# M515X.net
KiCad netlist of a schematic drawn in EAGLE
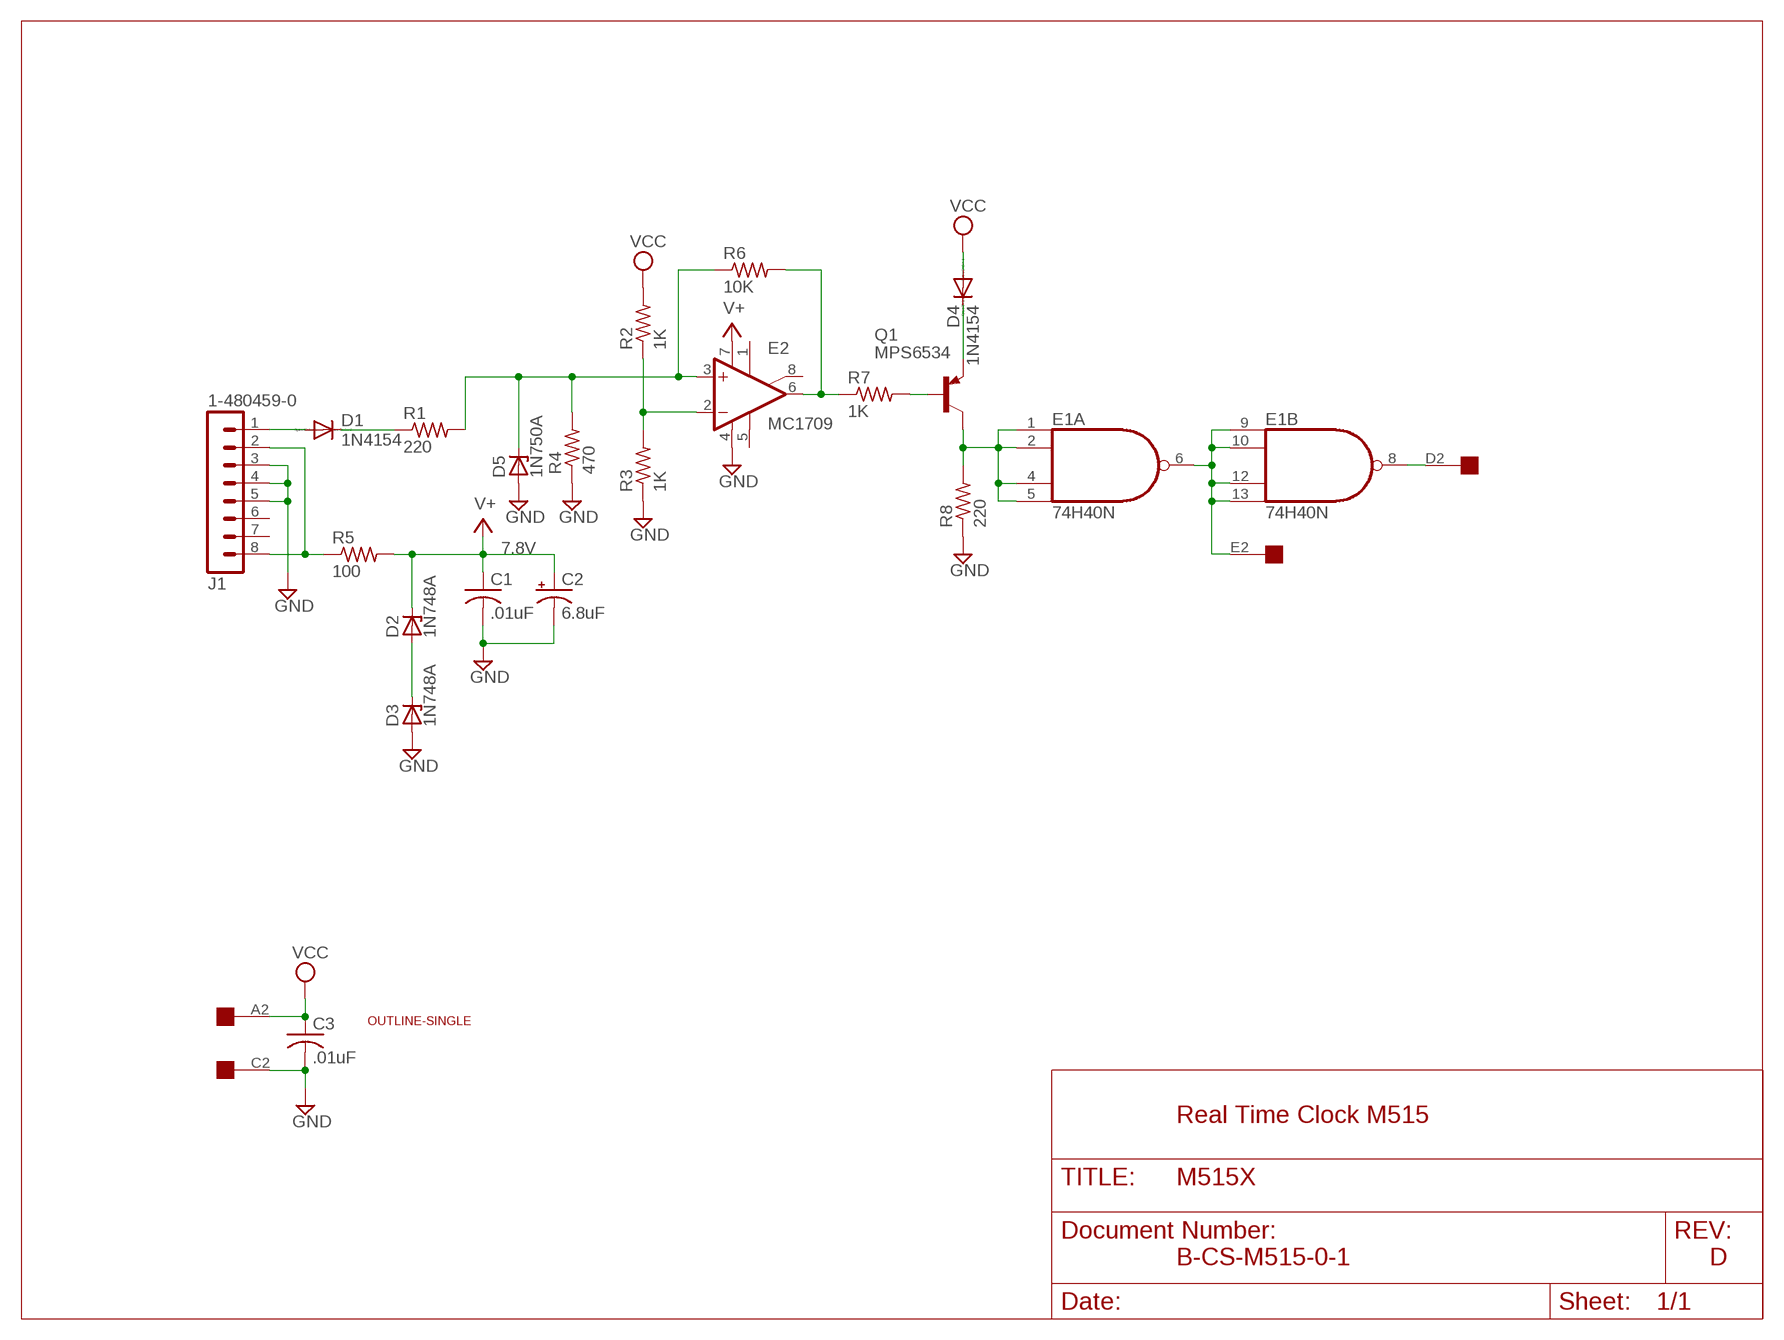
[diagram p0: schematic, sheet 1]

(export (version "E")
  (design (tool "Eeschema 10.0.6"))
  (components
    (comp (ref "C1")
      (value ".01uF")
      (footprint "eagle-import:C050-025X075")
      (libsource (lib "eagle-import") (part "C-US050-025X075"))
    )
    (comp (ref "C2")
      (value "6.8uF")
      (footprint "eagle-import:E12-8")
      (libsource (lib "eagle-import") (part "CPOL-USE20-8AXIAL"))
    )
    (comp (ref "C3")
      (value ".01uF")
      (footprint "eagle-import:C050-025X075")
      (libsource (lib "eagle-import") (part "C-US050-025X075"))
    )
    (comp (ref "D1")
      (value "1N4154")
      (footprint "eagle-import:DO35-10")
      (libsource (lib "eagle-import") (part "DIODE-DO35-10"))
    )
    (comp (ref "D2")
      (value "1N748A")
      (footprint "eagle-import:DO35Z10")
      (libsource (lib "eagle-import") (part "ZENER-DIODEDO35Z10"))
    )
    (comp (ref "D3")
      (value "1N748A")
      (footprint "eagle-import:DO35Z10")
      (libsource (lib "eagle-import") (part "ZENER-DIODEDO35Z10"))
    )
    (comp (ref "D4")
      (value "1N4154")
      (footprint "eagle-import:DO35-10")
      (libsource (lib "eagle-import") (part "DIODE-DO35-10"))
    )
    (comp (ref "D5")
      (value "1N750A")
      (footprint "eagle-import:DO35Z10")
      (libsource (lib "eagle-import") (part "ZENER-DIODEDO35Z10"))
    )
    (comp (ref "E1")
      (value "74H40N")
      (footprint "eagle-import:DIL14")
      (libsource (lib "eagle-import") (part "7440NS"))
    )
    (comp (ref "E2")
      (value "MC1709")
      (footprint "eagle-import:H08C")
      (libsource (lib "eagle-import") (part "MC1709"))
    )
    (comp (ref "J1")
      (value "1-480459-0")
      (footprint "eagle-import:1-480459-0")
      (libsource (lib "eagle-import") (part "1-480459-0"))
    )
    (comp (ref "Q1")
      (value "MPS6534")
      (footprint "eagle-import:TO5")
      (libsource (lib "eagle-import") (part "-PNP-TO5"))
    )
    (comp (ref "R1")
      (value "220")
      (footprint "eagle-import:0207_10")
      (libsource (lib "eagle-import") (part "R-US_0207/10"))
    )
    (comp (ref "R2")
      (value "1K")
      (footprint "eagle-import:0207_10")
      (libsource (lib "eagle-import") (part "R-US_0207/10"))
    )
    (comp (ref "R3")
      (value "1K")
      (footprint "eagle-import:0207_10")
      (libsource (lib "eagle-import") (part "R-US_0207/10"))
    )
    (comp (ref "R4")
      (value "470")
      (footprint "eagle-import:0207_10")
      (libsource (lib "eagle-import") (part "R-US_0207/10"))
    )
    (comp (ref "R5")
      (value "100")
      (footprint "eagle-import:0207_10")
      (libsource (lib "eagle-import") (part "R-US_0207/10"))
    )
    (comp (ref "R6")
      (value "10K")
      (footprint "eagle-import:0207_10")
      (libsource (lib "eagle-import") (part "R-US_0207/10"))
    )
    (comp (ref "R7")
      (value "1K")
      (footprint "eagle-import:0207_10")
      (libsource (lib "eagle-import") (part "R-US_0207/10"))
    )
    (comp (ref "R8")
      (value "220")
      (footprint "eagle-import:0207_10")
      (libsource (lib "eagle-import") (part "R-US_0207/10"))
    )
    (comp (ref "U$1")
      (value "OUTLINE-SINGLE")
      (footprint "eagle-import:SINGLE")
      (libsource (lib "eagle-import") (part "OUTLINE-SINGLE"))
    )
    (comp (ref "U$3")
      (value "EDGE-1")
      (footprint "eagle-import:EDGE-CON1")
      (libsource (lib "eagle-import") (part "EDGE-1"))
    )
  )
  (nets
    (net (code "1") (name "GND") (class "Default")
      (node (ref "C1") (pin "2") (pinfunction "2_2") (pintype "passive"))
      (node (ref "C2") (pin "-") (pinfunction "-_-") (pintype "passive"))
      (node (ref "C3") (pin "2") (pinfunction "2_2") (pintype "passive"))
      (node (ref "D3") (pin "A") (pinfunction "A_A") (pintype "passive"))
      (node (ref "D5") (pin "A") (pinfunction "A_A") (pintype "passive"))
      (node (ref "E2") (pin "4") (pinfunction "V-_4") (pintype "power_in"))
      (node (ref "J1") (pin "3") (pinfunction "3_3") (pintype "passive"))
      (node (ref "J1") (pin "4") (pinfunction "4_4") (pintype "passive"))
      (node (ref "J1") (pin "5") (pinfunction "5_5") (pintype "passive"))
      (node (ref "R3") (pin "1") (pinfunction "1_1") (pintype "passive"))
      (node (ref "R4") (pin "1") (pinfunction "1_1") (pintype "passive"))
      (node (ref "R8") (pin "1") (pinfunction "1_1") (pintype "passive"))
      (node (ref "U$3") (pin "C2") (pinfunction "1_C2") (pintype "bidirectional"))
    )
    (net (code "2") (name "Net-(D1-PadA)") (class "Default")
      (node (ref "D1") (pin "A") (pinfunction "A_A") (pintype "passive"))
      (node (ref "J1") (pin "1") (pinfunction "1_1") (pintype "passive"))
    )
    (net (code "3") (name "Net-(D1-PadC)") (class "Default")
      (node (ref "D1") (pin "C") (pinfunction "C_C") (pintype "passive"))
      (node (ref "R1") (pin "1") (pinfunction "1_1") (pintype "passive"))
    )
    (net (code "4") (name "Net-(D2-PadA)") (class "Default")
      (node (ref "D2") (pin "A") (pinfunction "A_A") (pintype "passive"))
      (node (ref "D3") (pin "C") (pinfunction "C_C") (pintype "passive"))
    )
    (net (code "5") (name "Net-(E1C-I0)") (class "Default")
      (node (ref "E1") (pin "1") (pinfunction "I0_1") (pintype "input"))
      (node (ref "E1") (pin "2") (pinfunction "I1_2") (pintype "input"))
      (node (ref "E1") (pin "4") (pinfunction "I2_4") (pintype "input"))
      (node (ref "E1") (pin "5") (pinfunction "I3_5") (pintype "input"))
      (node (ref "Q1") (pin "3") (pinfunction "C_3") (pintype "passive"))
      (node (ref "R8") (pin "2") (pinfunction "2_2") (pintype "passive"))
    )
    (net (code "6") (name "Net-(E1C-O)") (class "Default")
      (node (ref "E1") (pin "10") (pinfunction "I1_10") (pintype "input"))
      (node (ref "E1") (pin "12") (pinfunction "I2_12") (pintype "input"))
      (node (ref "E1") (pin "13") (pinfunction "I3_13") (pintype "input"))
      (node (ref "E1") (pin "6") (pinfunction "O_6") (pintype "output"))
      (node (ref "E1") (pin "9") (pinfunction "I0_9") (pintype "input"))
      (node (ref "U$3") (pin "E2") (pinfunction "1_E2") (pintype "bidirectional"))
    )
    (net (code "7") (name "Net-(E1D-O)") (class "Default")
      (node (ref "E1") (pin "8") (pinfunction "O_8") (pintype "output"))
      (node (ref "U$3") (pin "D2") (pinfunction "1_D2") (pintype "bidirectional"))
    )
    (net (code "8") (name "Net-(E2-+IN)") (class "Default")
      (node (ref "D5") (pin "C") (pinfunction "C_C") (pintype "passive"))
      (node (ref "E2") (pin "3") (pinfunction "+IN_3") (pintype "input"))
      (node (ref "R1") (pin "2") (pinfunction "2_2") (pintype "passive"))
      (node (ref "R4") (pin "2") (pinfunction "2_2") (pintype "passive"))
      (node (ref "R6") (pin "1") (pinfunction "1_1") (pintype "passive"))
    )
    (net (code "9") (name "Net-(E2--IN)") (class "Default")
      (node (ref "E2") (pin "2") (pinfunction "-IN_2") (pintype "input"))
      (node (ref "R2") (pin "1") (pinfunction "1_1") (pintype "passive"))
      (node (ref "R3") (pin "2") (pinfunction "2_2") (pintype "passive"))
    )
    (net (code "10") (name "Net-(E2-OUT)") (class "Default")
      (node (ref "E2") (pin "6") (pinfunction "OUT_6") (pintype "output"))
      (node (ref "R6") (pin "2") (pinfunction "2_2") (pintype "passive"))
      (node (ref "R7") (pin "1") (pinfunction "1_1") (pintype "passive"))
    )
    (net (code "11") (name "Net-(J1-Pad2)") (class "Default")
      (node (ref "J1") (pin "2") (pinfunction "2_2") (pintype "passive"))
      (node (ref "J1") (pin "8") (pinfunction "8_8") (pintype "passive"))
      (node (ref "R5") (pin "1") (pinfunction "1_1") (pintype "passive"))
    )
    (net (code "12") (name "Net-(Q1-B)") (class "Default")
      (node (ref "Q1") (pin "2") (pinfunction "B_2") (pintype "passive"))
      (node (ref "R7") (pin "2") (pinfunction "2_2") (pintype "passive"))
    )
    (net (code "13") (name "Net-(Q1-E)") (class "Default")
      (node (ref "D4") (pin "C") (pinfunction "C_C") (pintype "passive"))
      (node (ref "Q1") (pin "1") (pinfunction "E_1") (pintype "passive"))
    )
    (net (code "14") (name "V+") (class "Default")
      (node (ref "C1") (pin "1") (pinfunction "1_1") (pintype "passive"))
      (node (ref "C2") (pin "+") (pinfunction "+_+") (pintype "passive"))
      (node (ref "D2") (pin "C") (pinfunction "C_C") (pintype "passive"))
      (node (ref "E2") (pin "7") (pinfunction "V+_7") (pintype "power_in"))
      (node (ref "R5") (pin "2") (pinfunction "2_2") (pintype "passive"))
    )
    (net (code "15") (name "VCC") (class "Default")
      (node (ref "C3") (pin "1") (pinfunction "1_1") (pintype "passive"))
      (node (ref "D4") (pin "A") (pinfunction "A_A") (pintype "passive"))
      (node (ref "R2") (pin "2") (pinfunction "2_2") (pintype "passive"))
      (node (ref "U$3") (pin "A2") (pinfunction "1_A2") (pintype "bidirectional"))
    )
    (net (code "16") (name "unconnected-(E2-ON1-Pad1)") (class "Default")
      (node (ref "E2") (pin "1") (pinfunction "ON1_1") (pintype "passive"))
    )
    (net (code "17") (name "unconnected-(E2-ON2-Pad8)") (class "Default")
      (node (ref "E2") (pin "8") (pinfunction "ON2_8") (pintype "passive"))
    )
    (net (code "18") (name "unconnected-(E2-OPT-Pad5)") (class "Default")
      (node (ref "E2") (pin "5") (pinfunction "OPT_5") (pintype "passive"))
    )
    (net (code "19") (name "unconnected-(J1-Pad6)") (class "Default")
      (node (ref "J1") (pin "6") (pinfunction "6_6") (pintype "passive"))
    )
    (net (code "20") (name "unconnected-(J1-Pad7)") (class "Default")
      (node (ref "J1") (pin "7") (pinfunction "7_7") (pintype "passive"))
    )
  )
)
